# imu_3_xz.net
KiCad netlist of a schematic drawn in EAGLE
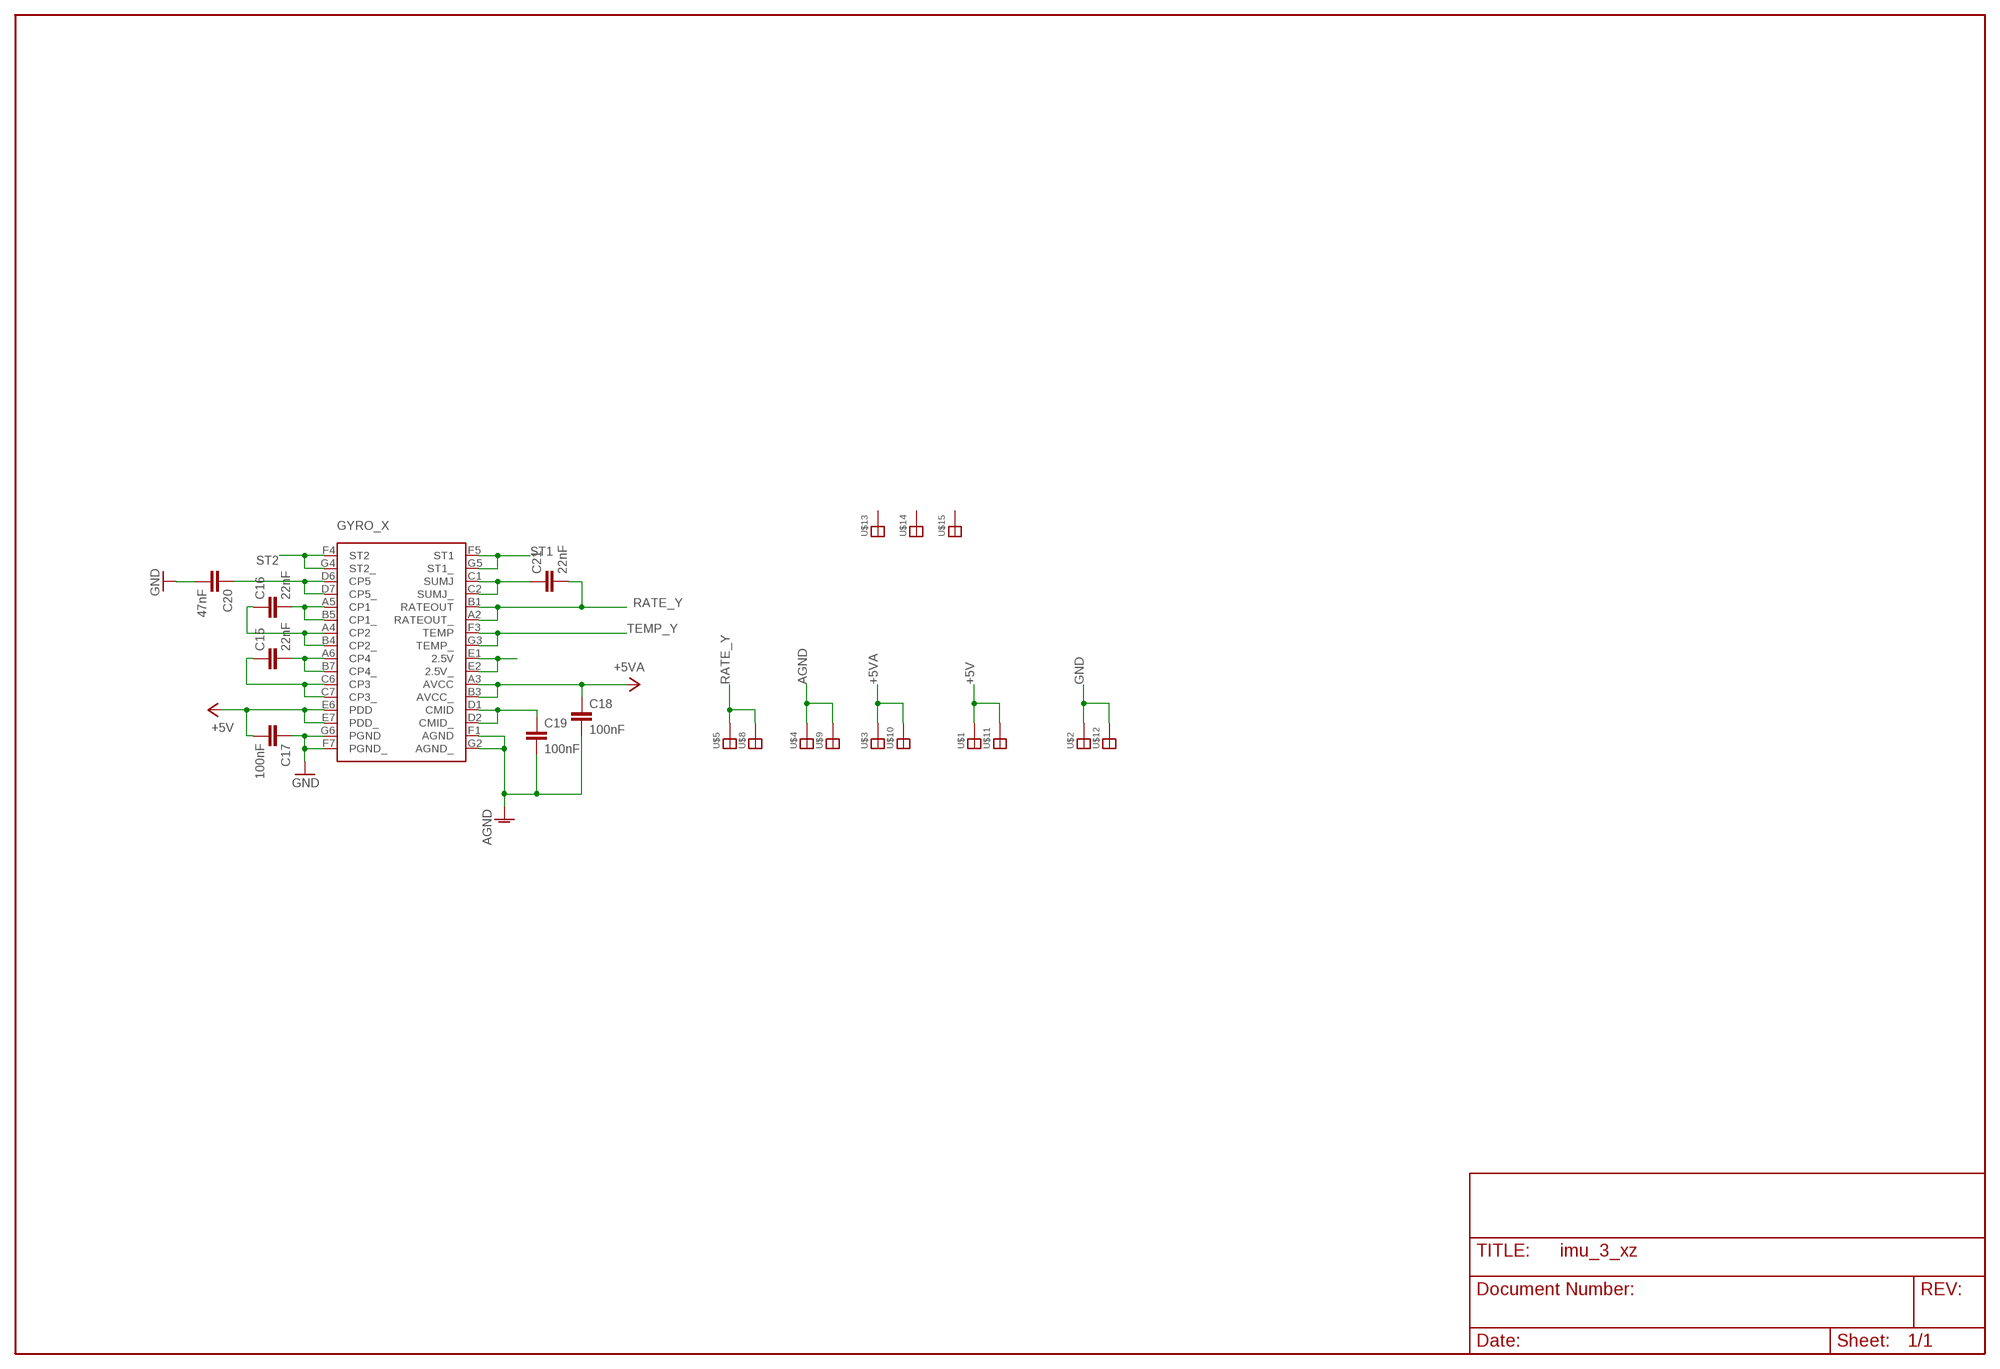
[diagram p0: schematic, sheet 1]

(export (version "E")
  (design (tool "Eeschema 10.0.6"))
  (components
    (comp (ref "C15")
      (value "22nF")
      (footprint "eagle-import:C0402K")
      (libsource (lib "eagle-import") (part "C-EUC0402K"))
    )
    (comp (ref "C16")
      (value "22nF")
      (footprint "eagle-import:C0402K")
      (libsource (lib "eagle-import") (part "C-EUC0402K"))
    )
    (comp (ref "C17")
      (value "100nF")
      (footprint "eagle-import:C0402K")
      (libsource (lib "eagle-import") (part "C-EUC0402K"))
    )
    (comp (ref "C18")
      (value "100nF")
      (footprint "eagle-import:C0402K")
      (libsource (lib "eagle-import") (part "C-EUC0402K"))
    )
    (comp (ref "C19")
      (value "100nF")
      (footprint "eagle-import:C0402K")
      (libsource (lib "eagle-import") (part "C-EUC0402K"))
    )
    (comp (ref "C20")
      (value "47nF")
      (footprint "eagle-import:C0402K")
      (libsource (lib "eagle-import") (part "C-EUC0402K"))
    )
    (comp (ref "C21")
      (value "22nF")
      (footprint "eagle-import:C0402K")
      (libsource (lib "eagle-import") (part "C-EUC0402K"))
    )
    (comp (ref "GYRO_X")
      (value "ADXR")
      (footprint "eagle-import:BC-32")
      (libsource (lib "eagle-import") (part "ADXR"))
    )
    (comp (ref "U$1")
      (value "SOLDER_PAD")
      (footprint "eagle-import:SOLDER_PAD")
      (libsource (lib "eagle-import") (part "SOLDER_PAD"))
    )
    (comp (ref "U$2")
      (value "SOLDER_PAD")
      (footprint "eagle-import:SOLDER_PAD")
      (libsource (lib "eagle-import") (part "SOLDER_PAD"))
    )
    (comp (ref "U$3")
      (value "SOLDER_PAD")
      (footprint "eagle-import:SOLDER_PAD")
      (libsource (lib "eagle-import") (part "SOLDER_PAD"))
    )
    (comp (ref "U$4")
      (value "SOLDER_PAD")
      (footprint "eagle-import:SOLDER_PAD")
      (libsource (lib "eagle-import") (part "SOLDER_PAD"))
    )
    (comp (ref "U$5")
      (value "SOLDER_PAD")
      (footprint "eagle-import:SOLDER_PAD")
      (libsource (lib "eagle-import") (part "SOLDER_PAD"))
    )
    (comp (ref "U$8")
      (value "SOLDER_PAD")
      (footprint "eagle-import:SOLDER_PAD")
      (libsource (lib "eagle-import") (part "SOLDER_PAD"))
    )
    (comp (ref "U$9")
      (value "SOLDER_PAD")
      (footprint "eagle-import:SOLDER_PAD")
      (libsource (lib "eagle-import") (part "SOLDER_PAD"))
    )
    (comp (ref "U$10")
      (value "SOLDER_PAD")
      (footprint "eagle-import:SOLDER_PAD")
      (libsource (lib "eagle-import") (part "SOLDER_PAD"))
    )
    (comp (ref "U$11")
      (value "SOLDER_PAD")
      (footprint "eagle-import:SOLDER_PAD")
      (libsource (lib "eagle-import") (part "SOLDER_PAD"))
    )
    (comp (ref "U$12")
      (value "SOLDER_PAD")
      (footprint "eagle-import:SOLDER_PAD")
      (libsource (lib "eagle-import") (part "SOLDER_PAD"))
    )
    (comp (ref "U$13")
      (value "SOLDER_PAD")
      (footprint "eagle-import:SOLDER_PAD")
      (libsource (lib "eagle-import") (part "SOLDER_PAD"))
    )
    (comp (ref "U$14")
      (value "SOLDER_PAD")
      (footprint "eagle-import:SOLDER_PAD")
      (libsource (lib "eagle-import") (part "SOLDER_PAD"))
    )
    (comp (ref "U$15")
      (value "SOLDER_PAD")
      (footprint "eagle-import:SOLDER_PAD")
      (libsource (lib "eagle-import") (part "SOLDER_PAD"))
    )
  )
  (nets
    (net (code "1") (name "+5V") (class "Default")
      (node (ref "C17") (pin "2") (pinfunction "2_2") (pintype "passive"))
      (node (ref "GYRO_X") (pin "E6") (pinfunction "PDD_E6") (pintype "bidirectional"))
      (node (ref "GYRO_X") (pin "E7") (pinfunction "PDD__E7") (pintype "bidirectional"))
      (node (ref "U$1") (pin "P$1") (pinfunction "P$1_P$1") (pintype "bidirectional"))
      (node (ref "U$11") (pin "P$1") (pinfunction "P$1_P$1") (pintype "bidirectional"))
    )
    (net (code "2") (name "+5VA") (class "Default")
      (node (ref "C18") (pin "1") (pinfunction "1_1") (pintype "passive"))
      (node (ref "GYRO_X") (pin "A3") (pinfunction "AVCC_A3") (pintype "bidirectional"))
      (node (ref "GYRO_X") (pin "B3") (pinfunction "AVCC__B3") (pintype "bidirectional"))
      (node (ref "U$10") (pin "P$1") (pinfunction "P$1_P$1") (pintype "bidirectional"))
      (node (ref "U$3") (pin "P$1") (pinfunction "P$1_P$1") (pintype "bidirectional"))
    )
    (net (code "3") (name "/RATE_Y") (class "Default")
      (node (ref "C21") (pin "2") (pinfunction "2_2") (pintype "passive"))
      (node (ref "GYRO_X") (pin "A2") (pinfunction "RATEOUT__A2") (pintype "bidirectional"))
      (node (ref "GYRO_X") (pin "B1") (pinfunction "RATEOUT_B1") (pintype "bidirectional"))
      (node (ref "U$5") (pin "P$1") (pinfunction "P$1_P$1") (pintype "bidirectional"))
      (node (ref "U$8") (pin "P$1") (pinfunction "P$1_P$1") (pintype "bidirectional"))
    )
    (net (code "4") (name "/ST1") (class "Default")
      (node (ref "GYRO_X") (pin "F5") (pinfunction "ST1_F5") (pintype "bidirectional"))
      (node (ref "GYRO_X") (pin "G5") (pinfunction "ST1__G5") (pintype "bidirectional"))
    )
    (net (code "5") (name "/ST2") (class "Default")
      (node (ref "GYRO_X") (pin "F4") (pinfunction "ST2_F4") (pintype "bidirectional"))
      (node (ref "GYRO_X") (pin "G4") (pinfunction "ST2__G4") (pintype "bidirectional"))
    )
    (net (code "6") (name "/TEMP_Y") (class "Default")
      (node (ref "GYRO_X") (pin "F3") (pinfunction "TEMP_F3") (pintype "bidirectional"))
      (node (ref "GYRO_X") (pin "G3") (pinfunction "TEMP__G3") (pintype "bidirectional"))
    )
    (net (code "7") (name "AGND") (class "Default")
      (node (ref "C18") (pin "2") (pinfunction "2_2") (pintype "passive"))
      (node (ref "C19") (pin "2") (pinfunction "2_2") (pintype "passive"))
      (node (ref "GYRO_X") (pin "F1") (pinfunction "AGND_F1") (pintype "bidirectional"))
      (node (ref "GYRO_X") (pin "G2") (pinfunction "AGND__G2") (pintype "bidirectional"))
      (node (ref "U$4") (pin "P$1") (pinfunction "P$1_P$1") (pintype "bidirectional"))
      (node (ref "U$9") (pin "P$1") (pinfunction "P$1_P$1") (pintype "bidirectional"))
    )
    (net (code "8") (name "GND") (class "Default")
      (node (ref "C17") (pin "1") (pinfunction "1_1") (pintype "passive"))
      (node (ref "C20") (pin "2") (pinfunction "2_2") (pintype "passive"))
      (node (ref "GYRO_X") (pin "F7") (pinfunction "PGND__F7") (pintype "bidirectional"))
      (node (ref "GYRO_X") (pin "G6") (pinfunction "PGND_G6") (pintype "bidirectional"))
      (node (ref "U$12") (pin "P$1") (pinfunction "P$1_P$1") (pintype "bidirectional"))
      (node (ref "U$2") (pin "P$1") (pinfunction "P$1_P$1") (pintype "bidirectional"))
    )
    (net (code "9") (name "Net-(GYRO_X-2.5V)") (class "Default")
      (node (ref "GYRO_X") (pin "E1") (pinfunction "2.5V_E1") (pintype "bidirectional"))
      (node (ref "GYRO_X") (pin "E2") (pinfunction "2.5V__E2") (pintype "bidirectional"))
    )
    (net (code "10") (name "Net-(GYRO_X-CMID)") (class "Default")
      (node (ref "C19") (pin "1") (pinfunction "1_1") (pintype "passive"))
      (node (ref "GYRO_X") (pin "D1") (pinfunction "CMID_D1") (pintype "bidirectional"))
      (node (ref "GYRO_X") (pin "D2") (pinfunction "CMID__D2") (pintype "bidirectional"))
    )
    (net (code "11") (name "Net-(GYRO_X-CP1)") (class "Default")
      (node (ref "C16") (pin "2") (pinfunction "2_2") (pintype "passive"))
      (node (ref "GYRO_X") (pin "A5") (pinfunction "CP1_A5") (pintype "bidirectional"))
      (node (ref "GYRO_X") (pin "B5") (pinfunction "CP1__B5") (pintype "bidirectional"))
    )
    (net (code "12") (name "Net-(GYRO_X-CP2)") (class "Default")
      (node (ref "C16") (pin "1") (pinfunction "1_1") (pintype "passive"))
      (node (ref "GYRO_X") (pin "A4") (pinfunction "CP2_A4") (pintype "bidirectional"))
      (node (ref "GYRO_X") (pin "B4") (pinfunction "CP2__B4") (pintype "bidirectional"))
    )
    (net (code "13") (name "Net-(GYRO_X-CP3)") (class "Default")
      (node (ref "C15") (pin "1") (pinfunction "1_1") (pintype "passive"))
      (node (ref "GYRO_X") (pin "C6") (pinfunction "CP3_C6") (pintype "bidirectional"))
      (node (ref "GYRO_X") (pin "C7") (pinfunction "CP3__C7") (pintype "bidirectional"))
    )
    (net (code "14") (name "Net-(GYRO_X-CP4)") (class "Default")
      (node (ref "C15") (pin "2") (pinfunction "2_2") (pintype "passive"))
      (node (ref "GYRO_X") (pin "A6") (pinfunction "CP4_A6") (pintype "bidirectional"))
      (node (ref "GYRO_X") (pin "B7") (pinfunction "CP4__B7") (pintype "bidirectional"))
    )
    (net (code "15") (name "Net-(GYRO_X-CP5)") (class "Default")
      (node (ref "C20") (pin "1") (pinfunction "1_1") (pintype "passive"))
      (node (ref "GYRO_X") (pin "D6") (pinfunction "CP5_D6") (pintype "bidirectional"))
      (node (ref "GYRO_X") (pin "D7") (pinfunction "CP5__D7") (pintype "bidirectional"))
    )
    (net (code "16") (name "Net-(GYRO_X-SUMJ)") (class "Default")
      (node (ref "C21") (pin "1") (pinfunction "1_1") (pintype "passive"))
      (node (ref "GYRO_X") (pin "C1") (pinfunction "SUMJ_C1") (pintype "bidirectional"))
      (node (ref "GYRO_X") (pin "C2") (pinfunction "SUMJ__C2") (pintype "bidirectional"))
    )
    (net (code "17") (name "unconnected-(U$13-PadP$1)") (class "Default")
      (node (ref "U$13") (pin "P$1") (pinfunction "P$1_P$1") (pintype "bidirectional"))
    )
    (net (code "18") (name "unconnected-(U$14-PadP$1)") (class "Default")
      (node (ref "U$14") (pin "P$1") (pinfunction "P$1_P$1") (pintype "bidirectional"))
    )
    (net (code "19") (name "unconnected-(U$15-PadP$1)") (class "Default")
      (node (ref "U$15") (pin "P$1") (pinfunction "P$1_P$1") (pintype "bidirectional"))
    )
  )
)
